# CH32V005F6P.net
KiCad netlist of a schematic drawn in Altium Designer
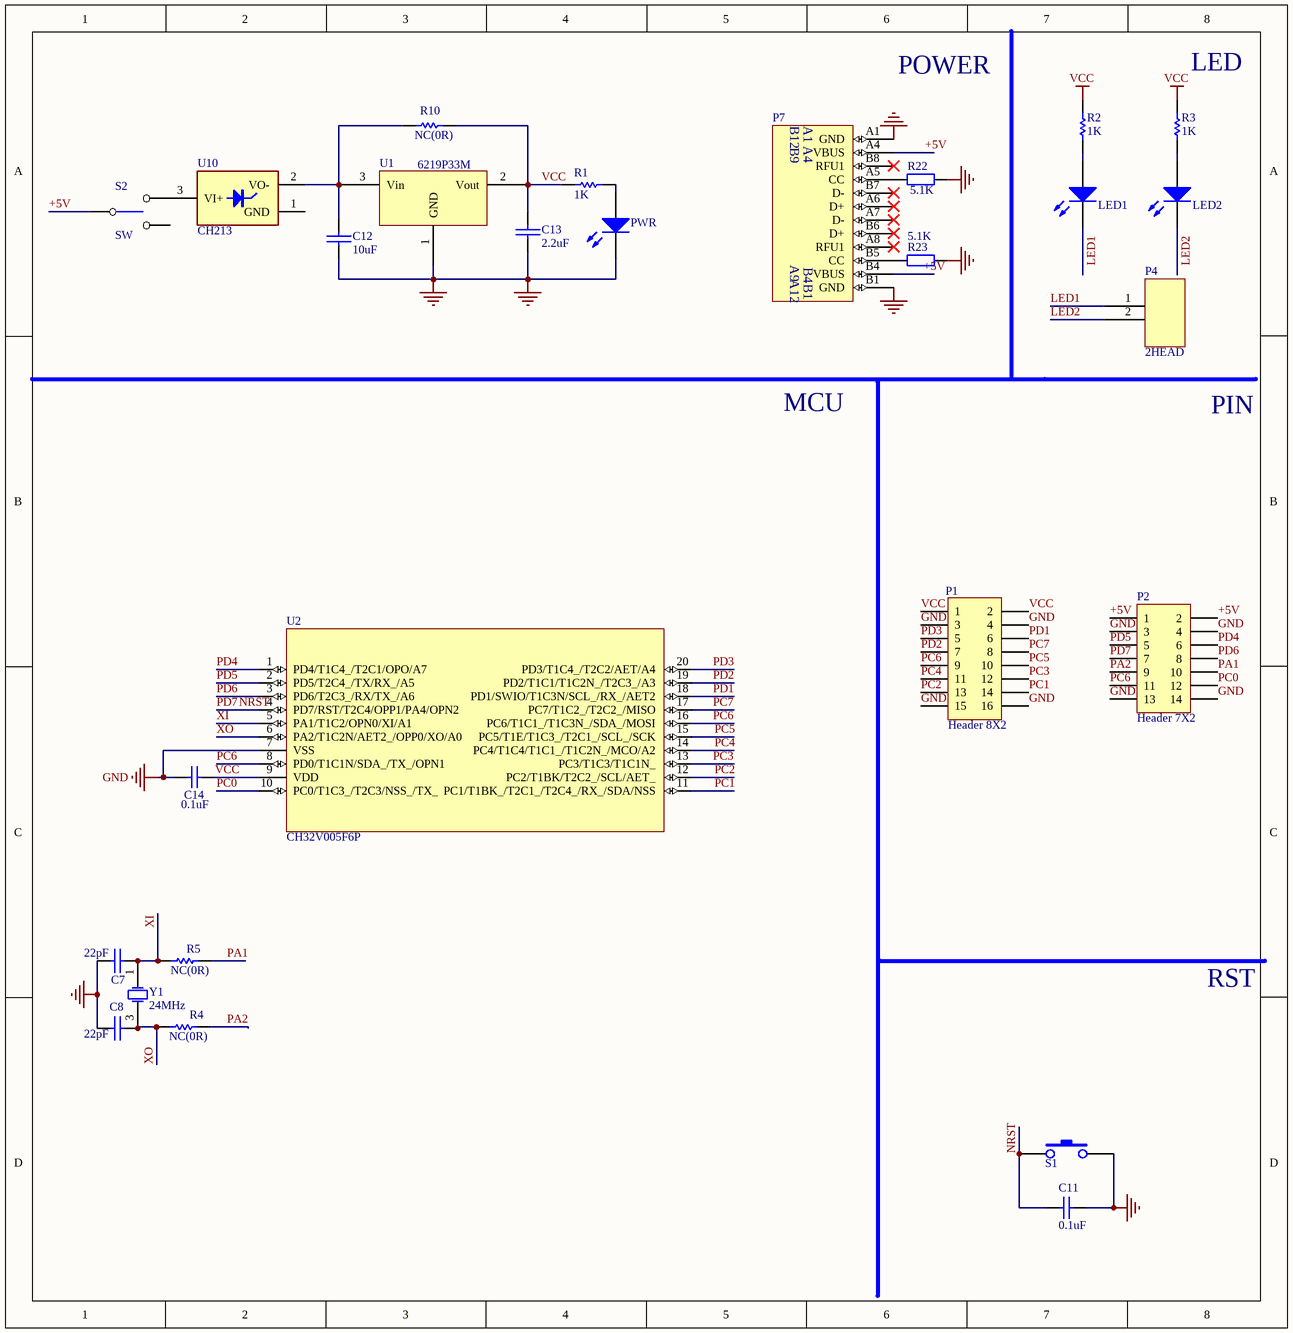
[diagram p0: CH32V005F6P.SchDoc]

(export (version "E")
  (design (tool "Eeschema 10.0.6"))
  (components
    (comp (ref "C7")
      (value "22pF")
      (footprint "0402_C")
      (description "Capacitor")
      (libsource (lib "*") (part "CAP"))
    )
    (comp (ref "C8")
      (value "22pF")
      (footprint "0402_C")
      (description "Capacitor")
      (libsource (lib "*") (part "CAP"))
    )
    (comp (ref "C11")
      (value "0.1uF")
      (footprint "0603_C")
      (description "Capacitor")
      (fields (field (name "PUBLISHER") "Altium Limited"))
      (libsource (lib "*") (part "Cap"))
    )
    (comp (ref "C12")
      (value "10uF")
      (footprint "0603_C")
      (description "Capacitor")
      (libsource (lib "wch_sch_others") (part "CAP"))
    )
    (comp (ref "C13")
      (value "2.2uF")
      (footprint "0402_C")
      (description "Capacitor")
      (libsource (lib "wch_sch_others") (part "CAP"))
    )
    (comp (ref "C14")
      (value "0.1uF")
      (footprint "0603_C")
      (description "Capacitor")
      (fields (field (name "PUBLISHER") "Altium Limited"))
      (libsource (lib "*") (part "Cap"))
    )
    (comp (ref "LED1")
      (value "LED1   blue")
      (footprint "0603+")
      (description "Typical INFRARED GaAs LED")
      (fields (field (name "PUBLISHER") "Altium Limited"))
      (libsource (lib "*") (part "LED0"))
    )
    (comp (ref "LED2")
      (value "LED2  blue")
      (footprint "0603+")
      (description "Typical INFRARED GaAs LED")
      (fields (field (name "PUBLISHER") "Altium Limited"))
      (libsource (lib "*") (part "LED0"))
    )
    (comp (ref "P1")
      (value "Header 8X2")
      (footprint "HDR2X8")
      (description "Header, 8-Pin, Dual row")
      (fields (field (name "PUBLISHER") "Altium Limited"))
      (libsource (lib "Miscellaneous Connectors") (part "Header 8X2"))
    )
    (comp (ref "P2")
      (value "Header 7X2")
      (footprint "HDR2X7")
      (description "Header, 7-Pin, Dual row")
      (fields (field (name "PUBLISHER") "Altium Limited"))
      (libsource (lib "Miscellaneous Connectors") (part "Header 7X2"))
    )
    (comp (ref "P4") (value "2HEAD") (footprint "SIP2-2.54mm") (libsource (lib "*") (part "2HEAD")))
    (comp (ref "P7")
      (value "TYPE-C")
      (footprint "TYPE-C-Receptacle-2.0")
      (libsource (lib "*") (part "TYPE-C1"))
    )
    (comp (ref "PWR")
      (value "POWER  red")
      (footprint "0603+")
      (description "Typical INFRARED GaAs LED")
      (fields (field (name "PUBLISHER") "Altium Limited"))
      (libsource (lib "") (part "LED0_1"))
    )
    (comp (ref "R1")
      (value "1K")
      (footprint "0402")
      (description "Semiconductor Resistor")
      (fields (field (name "PUBLISHER") "Altium Limited"))
      (libsource (lib "*") (part "Res Semi"))
    )
    (comp (ref "R2")
      (value "1K")
      (footprint "0402")
      (description "Semiconductor Resistor")
      (fields (field (name "PUBLISHER") "Altium Limited"))
      (libsource (lib "*") (part "Res Semi"))
    )
    (comp (ref "R3")
      (value "1K")
      (footprint "0402")
      (description "Semiconductor Resistor")
      (fields (field (name "PUBLISHER") "Altium Limited"))
      (libsource (lib "*") (part "Res Semi"))
    )
    (comp (ref "R4")
      (value "NC(0R)")
      (footprint "0402")
      (description "Semiconductor Resistor")
      (fields (field (name "Comment") "0R") (field (name "PUBLISHER") "Altium Limited"))
      (libsource (lib "*") (part "Res Semi"))
    )
    (comp (ref "R5")
      (value "NC(0R)")
      (footprint "0402")
      (description "Semiconductor Resistor")
      (fields (field (name "Comment") "0R") (field (name "PUBLISHER") "Altium Limited"))
      (libsource (lib "*") (part "Res Semi"))
    )
    (comp (ref "R10")
      (value "NC(0R)")
      (footprint "0402")
      (description "Semiconductor Resistor")
      (fields (field (name "Comment") "0R") (field (name "PUBLISHER") "Altium Limited"))
      (libsource (lib "*") (part "Res Semi"))
    )
    (comp (ref "R22")
      (value "5.1K")
      (footprint "0402")
      (description "Resistor")
      (libsource (lib "Miscellaneous Devices") (part "Res2"))
    )
    (comp (ref "R23")
      (value "5.1K")
      (footprint "0402")
      (description "Resistor")
      (libsource (lib "Miscellaneous Devices") (part "Res2"))
    )
    (comp (ref "S1") (value "NRST") (footprint "SMD_6.1x3.65x2.5mm-KEY") (libsource (lib "*") (part "KEY")))
    (comp (ref "S2") (value "SW") (footprint "SW1") (libsource (lib "*") (part "SW")))
    (comp (ref "U1")
      (value "6219P33M")
      (footprint "SOT-23")
      (libsource (lib "wch_sch_others") (part "6219P33M"))
    )
    (comp (ref "U2")
      (value "CH32V005F6P")
      (footprint "TSSOP20")
      (description "RISC-V MCU, 48MHz, ADC/OPA/2*UART/I2C/SPI")
      (libsource (lib "DHXXXSCH") (part "CH32V005F6P6"))
    )
    (comp (ref "U10")
      (value "CH213")
      (footprint "SOT-23-3")
      (description "Ideal Diode 5V*1A")
      (libsource (lib "CHXXX") (part "CH213E"))
    )
    (comp (ref "Y1")
      (value "24MHz")
      (footprint "XT3225")
      (description "Crystal Oscillator")
      (fields (field (name "PUBLISHER") "Altium Limited"))
      (libsource (lib "*") (part "XTAL"))
    )
  )
  (nets
    (net (code "1") (name "/+5V") (class "Default")
      (node (ref "P2") (pin "1") (pinfunction "1_1") (pintype "passive"))
      (node (ref "P2") (pin "2") (pinfunction "2_2") (pintype "passive"))
      (node (ref "P7") (pin "A4") (pinfunction "VBUS_A4") (pintype "bidirectional"))
      (node (ref "P7") (pin "B4") (pinfunction "VBUS_B4") (pintype "bidirectional"))
      (node (ref "S2") (pin "1") (pinfunction "1_1") (pintype "passive"))
    )
    (net (code "2") (name "/LED1") (class "Default")
      (node (ref "LED1") (pin "2") (pinfunction "K_2") (pintype "passive"))
      (node (ref "P4") (pin "1") (pintype "passive"))
    )
    (net (code "3") (name "/LED2") (class "Default")
      (node (ref "LED2") (pin "2") (pinfunction "K_2") (pintype "passive"))
      (node (ref "P4") (pin "2") (pintype "passive"))
    )
    (net (code "4") (name "/NRST") (class "Default")
      (node (ref "C11") (pin "2") (pinfunction "2_2") (pintype "passive"))
      (node (ref "P2") (pin "7") (pinfunction "7_7") (pintype "passive"))
      (node (ref "S1") (pin "1") (pinfunction "1_1") (pintype "passive"))
      (node (ref "U2") (pin "4") (pinfunction "PD7/RST/T2C4/OPP1/PA4/OPN2_4") (pintype "bidirectional"))
    )
    (net (code "5") (name "/PA1") (class "Default")
      (node (ref "P2") (pin "10") (pinfunction "10_10") (pintype "passive"))
      (node (ref "R5") (pin "2") (pinfunction "2_2") (pintype "passive"))
    )
    (net (code "6") (name "/PA2") (class "Default")
      (node (ref "P2") (pin "9") (pinfunction "9_9") (pintype "passive"))
      (node (ref "R4") (pin "2") (pinfunction "2_2") (pintype "passive"))
    )
    (net (code "7") (name "/PC0") (class "Default")
      (node (ref "P2") (pin "12") (pinfunction "12_12") (pintype "passive"))
      (node (ref "U2") (pin "10") (pinfunction "PC0/T1C3_/T2C3/NSS_/TX__10") (pintype "bidirectional"))
    )
    (net (code "8") (name "/PC1") (class "Default")
      (node (ref "P1") (pin "14") (pinfunction "14_14") (pintype "passive"))
      (node (ref "U2") (pin "11") (pinfunction "PC1/T1BK_/T2C1_/T2C4_/RX_/SDA/NSS_11") (pintype "bidirectional"))
    )
    (net (code "9") (name "/PC2") (class "Default")
      (node (ref "P1") (pin "13") (pinfunction "13_13") (pintype "passive"))
      (node (ref "U2") (pin "12") (pinfunction "PC2/T1BK/T2C2_/SCL/AET__12") (pintype "bidirectional"))
    )
    (net (code "10") (name "/PC3") (class "Default")
      (node (ref "P1") (pin "12") (pinfunction "12_12") (pintype "passive"))
      (node (ref "U2") (pin "13") (pinfunction "PC3/T1C3/T1C1N__13") (pintype "bidirectional"))
    )
    (net (code "11") (name "/PC4") (class "Default")
      (node (ref "P1") (pin "11") (pinfunction "11_11") (pintype "passive"))
      (node (ref "U2") (pin "14") (pinfunction "PC4/T1C4/T1C1_/T1C2N_/MCO/A2_14") (pintype "bidirectional"))
    )
    (net (code "12") (name "/PC5") (class "Default")
      (node (ref "P1") (pin "10") (pinfunction "10_10") (pintype "passive"))
      (node (ref "U2") (pin "15") (pinfunction "PC5/T1E/T1C3_/T2C1_/SCL_/SCK_15") (pintype "bidirectional"))
    )
    (net (code "13") (name "/PC6") (class "Default")
      (node (ref "P1") (pin "9") (pinfunction "9_9") (pintype "passive"))
      (node (ref "P2") (pin "11") (pinfunction "11_11") (pintype "passive"))
      (node (ref "U2") (pin "16") (pinfunction "PC6/T1C1_/T1C3N_/SDA_/MOSI_16") (pintype "bidirectional"))
      (node (ref "U2") (pin "8") (pinfunction "PD0/T1C1N/SDA_/TX_/OPN1_8") (pintype "bidirectional"))
    )
    (net (code "14") (name "/PC7") (class "Default")
      (node (ref "P1") (pin "8") (pinfunction "8_8") (pintype "passive"))
      (node (ref "U2") (pin "17") (pinfunction "PC7/T1C2_/T2C2_/MISO_17") (pintype "bidirectional"))
    )
    (net (code "15") (name "/PD1") (class "Default")
      (node (ref "P1") (pin "6") (pinfunction "6_6") (pintype "passive"))
      (node (ref "U2") (pin "18") (pinfunction "PD1/SWIO/T1C3N/SCL_/RX_/AET2_18") (pintype "bidirectional"))
    )
    (net (code "16") (name "/PD2") (class "Default")
      (node (ref "P1") (pin "7") (pinfunction "7_7") (pintype "passive"))
      (node (ref "U2") (pin "19") (pinfunction "PD2/T1C1/T1C2N_/T2C3_/A3_19") (pintype "bidirectional"))
    )
    (net (code "17") (name "/PD3") (class "Default")
      (node (ref "P1") (pin "5") (pinfunction "5_5") (pintype "passive"))
      (node (ref "U2") (pin "20") (pinfunction "PD3/T1C4_/T2C2/AET/A4_20") (pintype "bidirectional"))
    )
    (net (code "18") (name "/PD4") (class "Default")
      (node (ref "P2") (pin "6") (pinfunction "6_6") (pintype "passive"))
      (node (ref "U2") (pin "1") (pinfunction "PD4/T1C4_/T2C1/OPO/A7_1") (pintype "bidirectional"))
    )
    (net (code "19") (name "/PD5") (class "Default")
      (node (ref "P2") (pin "5") (pinfunction "5_5") (pintype "passive"))
      (node (ref "U2") (pin "2") (pinfunction "PD5/T2C4_/TX/RX_/A5_2") (pintype "bidirectional"))
    )
    (net (code "20") (name "/PD6") (class "Default")
      (node (ref "P2") (pin "8") (pinfunction "8_8") (pintype "passive"))
      (node (ref "U2") (pin "3") (pinfunction "PD6/T2C3_/RX/TX_/A6_3") (pintype "bidirectional"))
    )
    (net (code "21") (name "/XI") (class "Default")
      (node (ref "C7") (pin "2") (pinfunction "2_2") (pintype "passive"))
      (node (ref "R5") (pin "1") (pinfunction "1_1") (pintype "passive"))
      (node (ref "U2") (pin "5") (pinfunction "PA1/T1C2/OPN0/XI/A1_5") (pintype "bidirectional"))
      (node (ref "Y1") (pin "1") (pinfunction "OSC1_1") (pintype "passive"))
    )
    (net (code "22") (name "/XO") (class "Default")
      (node (ref "C8") (pin "2") (pinfunction "2_2") (pintype "passive"))
      (node (ref "R4") (pin "1") (pinfunction "1_1") (pintype "passive"))
      (node (ref "U2") (pin "6") (pinfunction "PA2/T1C2N/AET2_/OPP0/XO/A0_6") (pintype "bidirectional"))
      (node (ref "Y1") (pin "3") (pinfunction "OSC2_3") (pintype "passive"))
    )
    (net (code "23") (name "GND") (class "Default")
      (node (ref "C11") (pin "1") (pinfunction "1_1") (pintype "passive"))
      (node (ref "C12") (pin "2") (pinfunction "2_2") (pintype "passive"))
      (node (ref "C13") (pin "1") (pinfunction "1_1") (pintype "passive"))
      (node (ref "C14") (pin "2") (pinfunction "2_2") (pintype "passive"))
      (node (ref "C7") (pin "1") (pinfunction "1_1") (pintype "passive"))
      (node (ref "C8") (pin "1") (pinfunction "1_1") (pintype "passive"))
      (node (ref "P1") (pin "15") (pinfunction "15_15") (pintype "passive"))
      (node (ref "P1") (pin "16") (pinfunction "16_16") (pintype "passive"))
      (node (ref "P1") (pin "3") (pinfunction "3_3") (pintype "passive"))
      (node (ref "P1") (pin "4") (pinfunction "4_4") (pintype "passive"))
      (node (ref "P2") (pin "13") (pinfunction "13_13") (pintype "passive"))
      (node (ref "P2") (pin "14") (pinfunction "14_14") (pintype "passive"))
      (node (ref "P2") (pin "3") (pinfunction "3_3") (pintype "passive"))
      (node (ref "P2") (pin "4") (pinfunction "4_4") (pintype "passive"))
      (node (ref "P7") (pin "A1") (pinfunction "GND_A1") (pintype "bidirectional"))
      (node (ref "P7") (pin "B1") (pinfunction "GND_B1") (pintype "bidirectional"))
      (node (ref "PWR") (pin "2") (pinfunction "K_2") (pintype "passive"))
      (node (ref "R22") (pin "2") (pinfunction "2_2") (pintype "passive"))
      (node (ref "R23") (pin "2") (pinfunction "2_2") (pintype "passive"))
      (node (ref "S1") (pin "2") (pinfunction "2_2") (pintype "passive"))
      (node (ref "U1") (pin "1") (pinfunction "GND_1") (pintype "passive"))
      (node (ref "U2") (pin "7") (pinfunction "VSS_7") (pintype "power_in"))
    )
    (net (code "24") (name "Net-(LED1-A)") (class "Default")
      (node (ref "LED1") (pin "1") (pinfunction "A_1") (pintype "passive"))
      (node (ref "R2") (pin "2") (pinfunction "2_2") (pintype "passive"))
    )
    (net (code "25") (name "Net-(LED2-A)") (class "Default")
      (node (ref "LED2") (pin "1") (pinfunction "A_1") (pintype "passive"))
      (node (ref "R3") (pin "2") (pinfunction "2_2") (pintype "passive"))
    )
    (net (code "26") (name "Net-(P7-CC-PadA5)") (class "Default")
      (node (ref "P7") (pin "A5") (pinfunction "CC_A5") (pintype "bidirectional"))
      (node (ref "R22") (pin "1") (pinfunction "1_1") (pintype "passive"))
    )
    (net (code "27") (name "Net-(P7-CC-PadB5)") (class "Default")
      (node (ref "P7") (pin "B5") (pinfunction "CC_B5") (pintype "bidirectional"))
      (node (ref "R23") (pin "1") (pinfunction "1_1") (pintype "passive"))
    )
    (net (code "28") (name "Net-(PWR-A)") (class "Default")
      (node (ref "PWR") (pin "1") (pinfunction "A_1") (pintype "passive"))
      (node (ref "R1") (pin "1") (pinfunction "1_1") (pintype "passive"))
    )
    (net (code "29") (name "Net-(U1-Vin)") (class "Default")
      (node (ref "C12") (pin "1") (pinfunction "1_1") (pintype "passive"))
      (node (ref "R10") (pin "1") (pinfunction "1_1") (pintype "passive"))
      (node (ref "U1") (pin "3") (pinfunction "Vin_3") (pintype "passive"))
      (node (ref "U10") (pin "2") (pinfunction "VO-_2") (pintype "power_in"))
    )
    (net (code "30") (name "Net-(U10-VI+)") (class "Default")
      (node (ref "S2") (pin "3") (pinfunction "3_3") (pintype "passive"))
      (node (ref "U10") (pin "3") (pinfunction "VI+_3") (pintype "power_in"))
    )
    (net (code "31") (name "VCC") (class "Default")
      (node (ref "C13") (pin "2") (pinfunction "2_2") (pintype "passive"))
      (node (ref "C14") (pin "1") (pinfunction "1_1") (pintype "passive"))
      (node (ref "P1") (pin "1") (pinfunction "1_1") (pintype "passive"))
      (node (ref "P1") (pin "2") (pinfunction "2_2") (pintype "passive"))
      (node (ref "R1") (pin "2") (pinfunction "2_2") (pintype "passive"))
      (node (ref "R10") (pin "2") (pinfunction "2_2") (pintype "passive"))
      (node (ref "R2") (pin "1") (pinfunction "1_1") (pintype "passive"))
      (node (ref "R3") (pin "1") (pinfunction "1_1") (pintype "passive"))
      (node (ref "U1") (pin "2") (pinfunction "Vout_2") (pintype "passive"))
      (node (ref "U2") (pin "9") (pinfunction "VDD_9") (pintype "power_in"))
    )
    (net (code "32") (name "unconnected-(P7-D+-PadA6)") (class "Default")
      (node (ref "P7") (pin "A6") (pinfunction "D+_A6") (pintype "bidirectional+no_connect"))
    )
    (net (code "33") (name "unconnected-(P7-D+-PadB6)") (class "Default")
      (node (ref "P7") (pin "B6") (pinfunction "D+_B6") (pintype "bidirectional+no_connect"))
    )
    (net (code "34") (name "unconnected-(P7-D--PadA7)") (class "Default")
      (node (ref "P7") (pin "A7") (pinfunction "D-_A7") (pintype "bidirectional+no_connect"))
    )
    (net (code "35") (name "unconnected-(P7-D--PadB7)") (class "Default")
      (node (ref "P7") (pin "B7") (pinfunction "D-_B7") (pintype "bidirectional+no_connect"))
    )
    (net (code "36") (name "unconnected-(P7-RFU1-PadA8)") (class "Default")
      (node (ref "P7") (pin "A8") (pinfunction "RFU1_A8") (pintype "bidirectional+no_connect"))
    )
    (net (code "37") (name "unconnected-(P7-RFU1-PadB8)") (class "Default")
      (node (ref "P7") (pin "B8") (pinfunction "RFU1_B8") (pintype "bidirectional+no_connect"))
    )
    (net (code "38") (name "unconnected-(S2-Pad2)") (class "Default")
      (node (ref "S2") (pin "2") (pinfunction "2_2") (pintype "passive"))
    )
    (net (code "39") (name "unconnected-(U10-GND-Pad1)") (class "Default")
      (node (ref "U10") (pin "1") (pinfunction "GND_1") (pintype "power_in"))
    )
  )
)
